# coffe.net
KiCad netlist of a schematic drawn in EAGLE
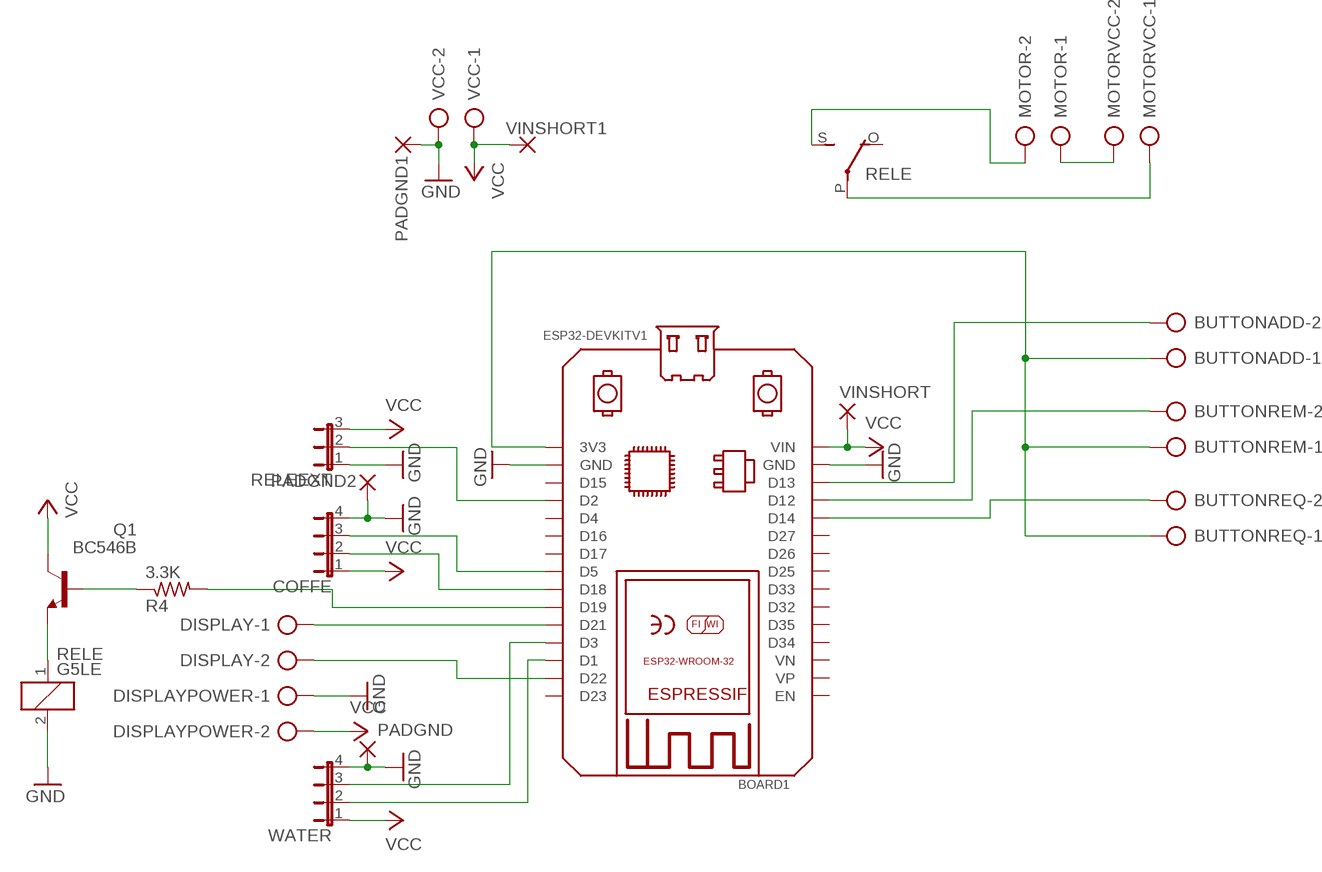
[diagram p0: schematic, sheet 1]

(export (version "E")
  (design (tool "Eeschema 10.0.6"))
  (components
    (comp (ref "BOARD1")
      (value "ESP32DEVKITV1")
      (footprint "eagle-import:ESP32-DEVKITV1")
      (libsource (lib "eagle-import") (part "ESP32DEVKITV1"))
    )
    (comp (ref "BUTTONADD")
      (value "AK500/2-H")
      (footprint "eagle-import:AK500_2-H")
      (libsource (lib "eagle-import") (part "AK500/2-H"))
    )
    (comp (ref "BUTTONREM")
      (value "AK500/2-H")
      (footprint "eagle-import:AK500_2-H")
      (libsource (lib "eagle-import") (part "AK500/2-H"))
    )
    (comp (ref "BUTTONREQ")
      (value "AK500/2-H")
      (footprint "eagle-import:AK500_2-H")
      (libsource (lib "eagle-import") (part "AK500/2-H"))
    )
    (comp (ref "COFFE")
      (value "JP4E")
      (footprint "eagle-import:JP4")
      (libsource (lib "eagle-import") (part "JP4E"))
    )
    (comp (ref "DISPLAY")
      (value "AK500/2-H")
      (footprint "eagle-import:AK500_2-H")
      (libsource (lib "eagle-import") (part "AK500/2-H"))
    )
    (comp (ref "DISPLAYPOWER")
      (value "AK500/2-H")
      (footprint "eagle-import:AK500_2-H")
      (libsource (lib "eagle-import") (part "AK500/2-H"))
    )
    (comp (ref "MOTOR")
      (value "AK500/2-H")
      (footprint "eagle-import:AK500_2-H")
      (libsource (lib "eagle-import") (part "AK500/2-H"))
    )
    (comp (ref "MOTORVCC")
      (value "AK500/2-H")
      (footprint "eagle-import:AK500_2-H")
      (libsource (lib "eagle-import") (part "AK500/2-H"))
    )
    (comp (ref "PADGND")
      (value "2,15/1,0")
      (footprint "eagle-import:2,15_1,0")
      (libsource (lib "eagle-import") (part "2,15/1,0"))
    )
    (comp (ref "PADGND1")
      (value "2,15/1,0")
      (footprint "eagle-import:2,15_1,0")
      (libsource (lib "eagle-import") (part "2,15/1,0"))
    )
    (comp (ref "PADGND2")
      (value "2,15/1,0")
      (footprint "eagle-import:2,15_1,0")
      (libsource (lib "eagle-import") (part "2,15/1,0"))
    )
    (comp (ref "Q1")
      (value "BC546B")
      (footprint "eagle-import:TO92-EBC")
      (libsource (lib "eagle-import") (part "BC546B"))
    )
    (comp (ref "R4")
      (value "3.3K")
      (footprint "eagle-import:0204_7")
      (libsource (lib "eagle-import") (part "R-US_0204/7"))
    )
    (comp (ref "RELE")
      (value "G5LE")
      (footprint "eagle-import:G5LE")
      (libsource (lib "eagle-import") (part "G5LE"))
    )
    (comp (ref "RELEEXT")
      (value "JP2E")
      (footprint "eagle-import:JP2")
      (libsource (lib "eagle-import") (part "JP2E"))
    )
    (comp (ref "VCC")
      (value "AK500/2-H")
      (footprint "eagle-import:AK500_2-H")
      (libsource (lib "eagle-import") (part "AK500/2-H"))
    )
    (comp (ref "VINSHORT")
      (value "2,15/1,0")
      (footprint "eagle-import:2,15_1,0")
      (libsource (lib "eagle-import") (part "2,15/1,0"))
    )
    (comp (ref "VINSHORT1")
      (value "2,15/1,0")
      (footprint "eagle-import:2,15_1,0")
      (libsource (lib "eagle-import") (part "2,15/1,0"))
    )
    (comp (ref "WATER")
      (value "JP4E")
      (footprint "eagle-import:JP4")
      (libsource (lib "eagle-import") (part "JP4E"))
    )
  )
  (nets
    (net (code "1") (name "GND") (class "Default")
      (node (ref "BOARD1") (pin "GND") (pinfunction "GND_GND") (pintype "bidirectional"))
      (node (ref "BOARD1") (pin "GND@1") (pinfunction "GND_GND@1") (pintype "bidirectional"))
      (node (ref "COFFE") (pin "4") (pinfunction "4_4") (pintype "passive"))
      (node (ref "DISPLAYPOWER") (pin "1") (pinfunction "KL_1") (pintype "passive"))
      (node (ref "PADGND") (pin "1") (pinfunction "P_1") (pintype "passive"))
      (node (ref "PADGND1") (pin "1") (pinfunction "P_1") (pintype "passive"))
      (node (ref "PADGND2") (pin "1") (pinfunction "P_1") (pintype "passive"))
      (node (ref "RELE") (pin "2") (pinfunction "2_2") (pintype "passive"))
      (node (ref "RELEEXT") (pin "1") (pinfunction "1_1") (pintype "passive"))
      (node (ref "VCC") (pin "2") (pinfunction "KL_2") (pintype "passive"))
      (node (ref "WATER") (pin "4") (pinfunction "4_4") (pintype "passive"))
    )
    (net (code "2") (name "Net-(BOARD1-PadD1)") (class "Default")
      (node (ref "BOARD1") (pin "D1") (pinfunction "D1_D1") (pintype "bidirectional"))
      (node (ref "WATER") (pin "2") (pinfunction "2_2") (pintype "passive"))
    )
    (net (code "3") (name "Net-(BOARD1-PadD2)") (class "Default")
      (node (ref "BOARD1") (pin "D2") (pinfunction "D2_D2") (pintype "bidirectional"))
      (node (ref "RELEEXT") (pin "2") (pinfunction "2_2") (pintype "passive"))
    )
    (net (code "4") (name "Net-(BOARD1-PadD3)") (class "Default")
      (node (ref "BOARD1") (pin "D3") (pinfunction "D3_D3") (pintype "bidirectional"))
      (node (ref "WATER") (pin "3") (pinfunction "3_3") (pintype "passive"))
    )
    (net (code "5") (name "Net-(BOARD1-PadD5)") (class "Default")
      (node (ref "BOARD1") (pin "D5") (pinfunction "D5_D5") (pintype "bidirectional"))
      (node (ref "COFFE") (pin "3") (pinfunction "3_3") (pintype "passive"))
    )
    (net (code "6") (name "Net-(BOARD1-PadD18)") (class "Default")
      (node (ref "BOARD1") (pin "D18") (pinfunction "D18_D18") (pintype "bidirectional"))
      (node (ref "COFFE") (pin "2") (pinfunction "2_2") (pintype "passive"))
    )
    (net (code "7") (name "Net-(BOARD1-PadD19)") (class "Default")
      (node (ref "BOARD1") (pin "D19") (pinfunction "D19_D19") (pintype "bidirectional"))
      (node (ref "R4") (pin "2") (pinfunction "2_2") (pintype "passive"))
    )
    (net (code "8") (name "Net-(BUTTONADDA-KL)") (class "Default")
      (node (ref "BOARD1") (pin "3V3") (pinfunction "3V3_3V3") (pintype "bidirectional"))
      (node (ref "BUTTONADD") (pin "1") (pinfunction "KL_1") (pintype "passive"))
      (node (ref "BUTTONREM") (pin "1") (pinfunction "KL_1") (pintype "passive"))
      (node (ref "BUTTONREQ") (pin "1") (pinfunction "KL_1") (pintype "passive"))
    )
    (net (code "9") (name "Net-(BUTTONADDB-KL)") (class "Default")
      (node (ref "BOARD1") (pin "D13") (pinfunction "D13_D13") (pintype "bidirectional"))
      (node (ref "BUTTONADD") (pin "2") (pinfunction "KL_2") (pintype "passive"))
    )
    (net (code "10") (name "Net-(BUTTONREMB-KL)") (class "Default")
      (node (ref "BOARD1") (pin "D12") (pinfunction "D12_D12") (pintype "bidirectional"))
      (node (ref "BUTTONREM") (pin "2") (pinfunction "KL_2") (pintype "passive"))
    )
    (net (code "11") (name "Net-(BUTTONREQB-KL)") (class "Default")
      (node (ref "BOARD1") (pin "D14") (pinfunction "D14_D14") (pintype "bidirectional"))
      (node (ref "BUTTONREQ") (pin "2") (pinfunction "KL_2") (pintype "passive"))
    )
    (net (code "12") (name "Net-(DISPLAYA-KL)") (class "Default")
      (node (ref "BOARD1") (pin "D21") (pinfunction "D21_D21") (pintype "bidirectional"))
      (node (ref "DISPLAY") (pin "1") (pinfunction "KL_1") (pintype "passive"))
    )
    (net (code "13") (name "Net-(DISPLAYB-KL)") (class "Default")
      (node (ref "BOARD1") (pin "D22") (pinfunction "D22_D22") (pintype "bidirectional"))
      (node (ref "DISPLAY") (pin "2") (pinfunction "KL_2") (pintype "passive"))
    )
    (net (code "14") (name "Net-(MOTORA-KL)") (class "Default")
      (node (ref "MOTOR") (pin "1") (pinfunction "KL_1") (pintype "passive"))
      (node (ref "MOTORVCC") (pin "2") (pinfunction "KL_2") (pintype "passive"))
    )
    (net (code "15") (name "Net-(MOTORB-KL)") (class "Default")
      (node (ref "MOTOR") (pin "2") (pinfunction "KL_2") (pintype "passive"))
      (node (ref "RELE") (pin "S") (pinfunction "S_S") (pintype "passive"))
    )
    (net (code "16") (name "Net-(MOTORVCCA-KL)") (class "Default")
      (node (ref "MOTORVCC") (pin "1") (pinfunction "KL_1") (pintype "passive"))
      (node (ref "RELE") (pin "P") (pinfunction "P_P") (pintype "passive"))
    )
    (net (code "17") (name "Net-(Q1-PadB)") (class "Default")
      (node (ref "Q1") (pin "B") (pinfunction "B_B") (pintype "passive"))
      (node (ref "R4") (pin "1") (pinfunction "1_1") (pintype "passive"))
    )
    (net (code "18") (name "Net-(Q1-PadE)") (class "Default")
      (node (ref "Q1") (pin "E") (pinfunction "E_E") (pintype "passive"))
      (node (ref "RELE") (pin "1") (pinfunction "1_1") (pintype "passive"))
    )
    (net (code "19") (name "VCC") (class "Default")
      (node (ref "BOARD1") (pin "VIN") (pinfunction "VIN_VIN") (pintype "bidirectional"))
      (node (ref "COFFE") (pin "1") (pinfunction "1_1") (pintype "passive"))
      (node (ref "DISPLAYPOWER") (pin "2") (pinfunction "KL_2") (pintype "passive"))
      (node (ref "Q1") (pin "C") (pinfunction "C_C") (pintype "passive"))
      (node (ref "RELEEXT") (pin "3") (pinfunction "3_3") (pintype "passive"))
      (node (ref "VCC") (pin "1") (pinfunction "KL_1") (pintype "passive"))
      (node (ref "VINSHORT") (pin "1") (pinfunction "P_1") (pintype "passive"))
      (node (ref "VINSHORT1") (pin "1") (pinfunction "P_1") (pintype "passive"))
      (node (ref "WATER") (pin "1") (pinfunction "1_1") (pintype "passive"))
    )
    (net (code "20") (name "unconnected-(BOARD1-PadD4)") (class "Default")
      (node (ref "BOARD1") (pin "D4") (pinfunction "D4_D4") (pintype "bidirectional"))
    )
    (net (code "21") (name "unconnected-(BOARD1-PadD15)") (class "Default")
      (node (ref "BOARD1") (pin "D15") (pinfunction "D15_D15") (pintype "bidirectional"))
    )
    (net (code "22") (name "unconnected-(BOARD1-PadD16)") (class "Default")
      (node (ref "BOARD1") (pin "D16") (pinfunction "D16_D16") (pintype "bidirectional"))
    )
    (net (code "23") (name "unconnected-(BOARD1-PadD17)") (class "Default")
      (node (ref "BOARD1") (pin "D17") (pinfunction "D17_D17") (pintype "bidirectional"))
    )
    (net (code "24") (name "unconnected-(BOARD1-PadD23)") (class "Default")
      (node (ref "BOARD1") (pin "D23") (pinfunction "D23_D23") (pintype "bidirectional"))
    )
    (net (code "25") (name "unconnected-(BOARD1-PadD25)") (class "Default")
      (node (ref "BOARD1") (pin "D25") (pinfunction "D25_D25") (pintype "bidirectional"))
    )
    (net (code "26") (name "unconnected-(BOARD1-PadD26)") (class "Default")
      (node (ref "BOARD1") (pin "D26") (pinfunction "D26_D26") (pintype "bidirectional"))
    )
    (net (code "27") (name "unconnected-(BOARD1-PadD27)") (class "Default")
      (node (ref "BOARD1") (pin "D27") (pinfunction "D27_D27") (pintype "bidirectional"))
    )
    (net (code "28") (name "unconnected-(BOARD1-PadD32)") (class "Default")
      (node (ref "BOARD1") (pin "D32") (pinfunction "D32_D32") (pintype "bidirectional"))
    )
    (net (code "29") (name "unconnected-(BOARD1-PadD33)") (class "Default")
      (node (ref "BOARD1") (pin "D33") (pinfunction "D33_D33") (pintype "bidirectional"))
    )
    (net (code "30") (name "unconnected-(BOARD1-PadD34)") (class "Default")
      (node (ref "BOARD1") (pin "D34") (pinfunction "D34_D34") (pintype "bidirectional"))
    )
    (net (code "31") (name "unconnected-(BOARD1-PadD35)") (class "Default")
      (node (ref "BOARD1") (pin "D35") (pinfunction "D35_D35") (pintype "bidirectional"))
    )
    (net (code "32") (name "unconnected-(BOARD1-PadEN)") (class "Default")
      (node (ref "BOARD1") (pin "EN") (pinfunction "EN_EN") (pintype "bidirectional"))
    )
    (net (code "33") (name "unconnected-(BOARD1-PadVN)") (class "Default")
      (node (ref "BOARD1") (pin "VN") (pinfunction "VN_VN") (pintype "bidirectional"))
    )
    (net (code "34") (name "unconnected-(BOARD1-PadVP)") (class "Default")
      (node (ref "BOARD1") (pin "VP") (pinfunction "VP_VP") (pintype "bidirectional"))
    )
    (net (code "35") (name "unconnected-(RELE-PadO)") (class "Default")
      (node (ref "RELE") (pin "O") (pinfunction "O_O") (pintype "passive"))
    )
  )
)
